# martix_connect.net
KiCad netlist of a schematic drawn in Altium Designer
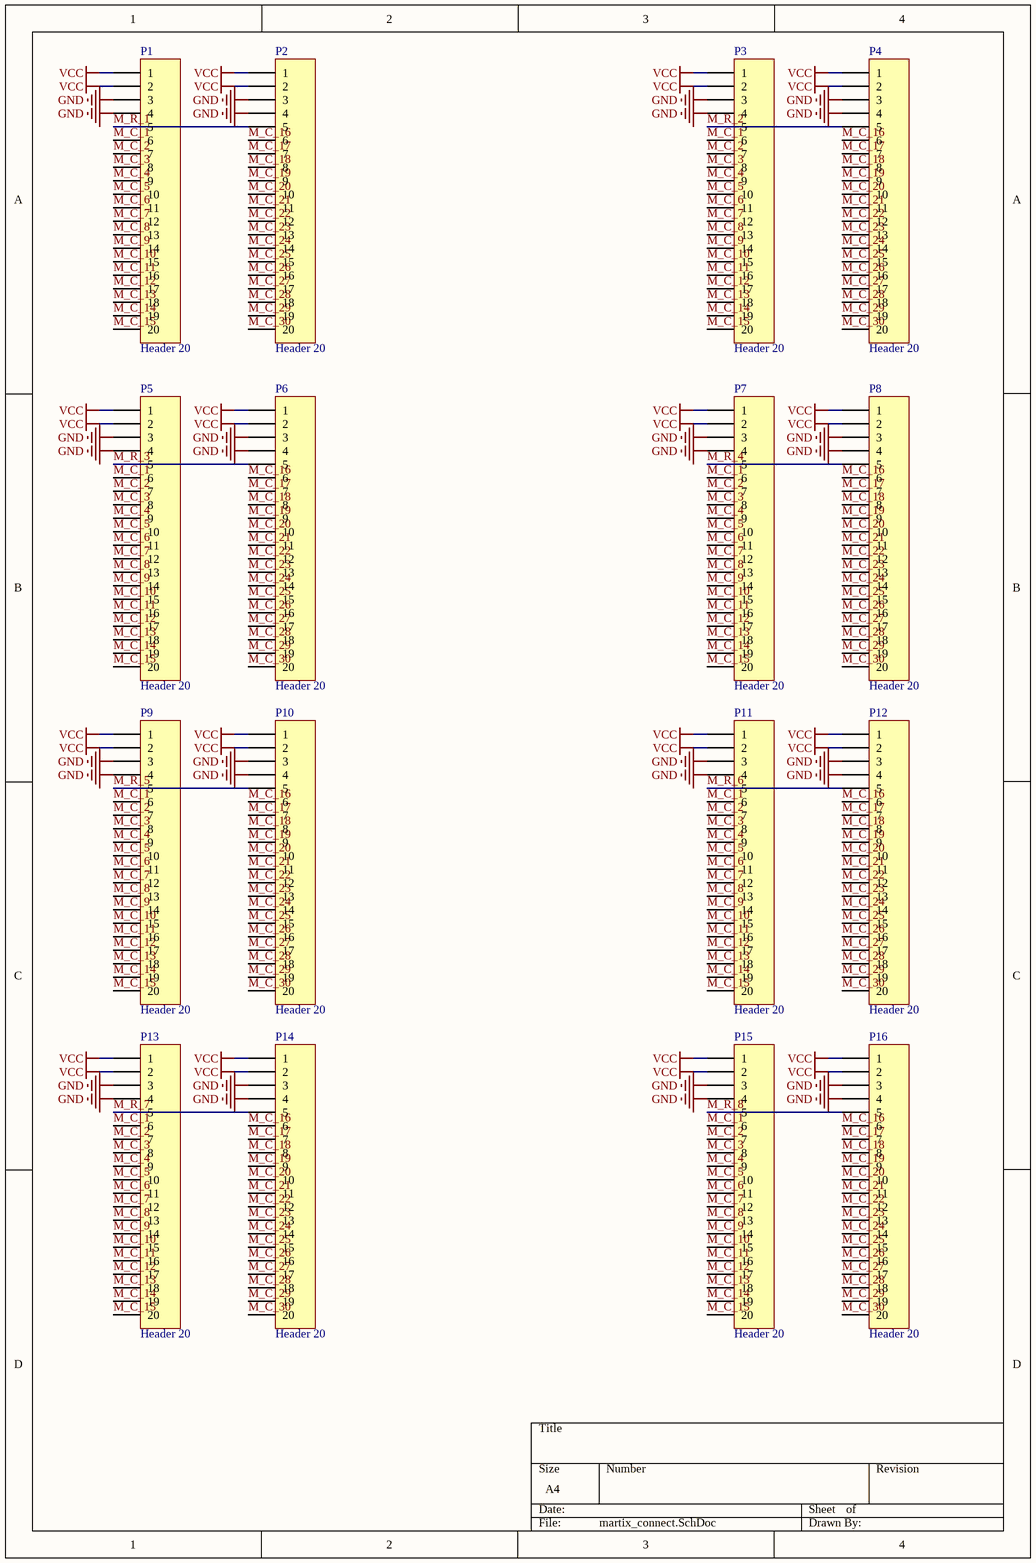
[diagram p0: martix_connect.SchDoc]

(export (version "E")
  (design (tool "Eeschema 10.0.6"))
  (components
    (comp (ref "P1")
      (value "Header 20")
      (footprint "FPC0.5 2H-WS-20P")
      (description "Header, 20-Pin")
      (fields (field (name "PUBLISHER") "Altium Limited"))
      (libsource (lib "Miscellaneous Connectors") (part "Header 20"))
    )
    (comp (ref "P2")
      (value "Header 20")
      (footprint "FPC0.5 2H-WS-20P")
      (description "Header, 20-Pin")
      (fields (field (name "PUBLISHER") "Altium Limited"))
      (libsource (lib "Miscellaneous Connectors") (part "Header 20"))
    )
    (comp (ref "P3")
      (value "Header 20")
      (footprint "FPC0.5 2H-WS-20P")
      (description "Header, 20-Pin")
      (fields (field (name "PUBLISHER") "Altium Limited"))
      (libsource (lib "Miscellaneous Connectors") (part "Header 20"))
    )
    (comp (ref "P4")
      (value "Header 20")
      (footprint "FPC0.5 2H-WS-20P")
      (description "Header, 20-Pin")
      (fields (field (name "PUBLISHER") "Altium Limited"))
      (libsource (lib "Miscellaneous Connectors") (part "Header 20"))
    )
    (comp (ref "P5")
      (value "Header 20")
      (footprint "FPC0.5 2H-WS-20P")
      (description "Header, 20-Pin")
      (fields (field (name "PUBLISHER") "Altium Limited"))
      (libsource (lib "Miscellaneous Connectors") (part "Header 20"))
    )
    (comp (ref "P6")
      (value "Header 20")
      (footprint "FPC0.5 2H-WS-20P")
      (description "Header, 20-Pin")
      (fields (field (name "PUBLISHER") "Altium Limited"))
      (libsource (lib "Miscellaneous Connectors") (part "Header 20"))
    )
    (comp (ref "P7")
      (value "Header 20")
      (footprint "FPC0.5 2H-WS-20P")
      (description "Header, 20-Pin")
      (fields (field (name "PUBLISHER") "Altium Limited"))
      (libsource (lib "Miscellaneous Connectors") (part "Header 20"))
    )
    (comp (ref "P8")
      (value "Header 20")
      (footprint "FPC0.5 2H-WS-20P")
      (description "Header, 20-Pin")
      (fields (field (name "PUBLISHER") "Altium Limited"))
      (libsource (lib "Miscellaneous Connectors") (part "Header 20"))
    )
    (comp (ref "P9")
      (value "Header 20")
      (footprint "FPC0.5 2H-WS-20P")
      (description "Header, 20-Pin")
      (fields (field (name "PUBLISHER") "Altium Limited"))
      (libsource (lib "Miscellaneous Connectors") (part "Header 20"))
    )
    (comp (ref "P10")
      (value "Header 20")
      (footprint "FPC0.5 2H-WS-20P")
      (description "Header, 20-Pin")
      (fields (field (name "PUBLISHER") "Altium Limited"))
      (libsource (lib "Miscellaneous Connectors") (part "Header 20"))
    )
    (comp (ref "P11")
      (value "Header 20")
      (footprint "FPC0.5 2H-WS-20P")
      (description "Header, 20-Pin")
      (fields (field (name "PUBLISHER") "Altium Limited"))
      (libsource (lib "Miscellaneous Connectors") (part "Header 20"))
    )
    (comp (ref "P12")
      (value "Header 20")
      (footprint "FPC0.5 2H-WS-20P")
      (description "Header, 20-Pin")
      (fields (field (name "PUBLISHER") "Altium Limited"))
      (libsource (lib "Miscellaneous Connectors") (part "Header 20"))
    )
    (comp (ref "P13")
      (value "Header 20")
      (footprint "FPC0.5 2H-WS-20P")
      (description "Header, 20-Pin")
      (fields (field (name "PUBLISHER") "Altium Limited"))
      (libsource (lib "Miscellaneous Connectors") (part "Header 20"))
    )
    (comp (ref "P14")
      (value "Header 20")
      (footprint "FPC0.5 2H-WS-20P")
      (description "Header, 20-Pin")
      (fields (field (name "PUBLISHER") "Altium Limited"))
      (libsource (lib "Miscellaneous Connectors") (part "Header 20"))
    )
    (comp (ref "P15")
      (value "Header 20")
      (footprint "FPC0.5 2H-WS-20P")
      (description "Header, 20-Pin")
      (fields (field (name "PUBLISHER") "Altium Limited"))
      (libsource (lib "Miscellaneous Connectors") (part "Header 20"))
    )
    (comp (ref "P16")
      (value "Header 20")
      (footprint "FPC0.5 2H-WS-20P")
      (description "Header, 20-Pin")
      (fields (field (name "PUBLISHER") "Altium Limited"))
      (libsource (lib "Miscellaneous Connectors") (part "Header 20"))
    )
  )
  (nets
    (net (code "1") (name "/M_C_1") (class "Default")
      (node (ref "P1") (pin "6") (pinfunction "6_6") (pintype "passive"))
      (node (ref "P11") (pin "6") (pinfunction "6_6") (pintype "passive"))
      (node (ref "P13") (pin "6") (pinfunction "6_6") (pintype "passive"))
      (node (ref "P15") (pin "6") (pinfunction "6_6") (pintype "passive"))
      (node (ref "P3") (pin "6") (pinfunction "6_6") (pintype "passive"))
      (node (ref "P5") (pin "6") (pinfunction "6_6") (pintype "passive"))
      (node (ref "P7") (pin "6") (pinfunction "6_6") (pintype "passive"))
      (node (ref "P9") (pin "6") (pinfunction "6_6") (pintype "passive"))
    )
    (net (code "2") (name "/M_C_2") (class "Default")
      (node (ref "P1") (pin "7") (pinfunction "7_7") (pintype "passive"))
      (node (ref "P11") (pin "7") (pinfunction "7_7") (pintype "passive"))
      (node (ref "P13") (pin "7") (pinfunction "7_7") (pintype "passive"))
      (node (ref "P15") (pin "7") (pinfunction "7_7") (pintype "passive"))
      (node (ref "P3") (pin "7") (pinfunction "7_7") (pintype "passive"))
      (node (ref "P5") (pin "7") (pinfunction "7_7") (pintype "passive"))
      (node (ref "P7") (pin "7") (pinfunction "7_7") (pintype "passive"))
      (node (ref "P9") (pin "7") (pinfunction "7_7") (pintype "passive"))
    )
    (net (code "3") (name "/M_C_3") (class "Default")
      (node (ref "P1") (pin "8") (pinfunction "8_8") (pintype "passive"))
      (node (ref "P11") (pin "8") (pinfunction "8_8") (pintype "passive"))
      (node (ref "P13") (pin "8") (pinfunction "8_8") (pintype "passive"))
      (node (ref "P15") (pin "8") (pinfunction "8_8") (pintype "passive"))
      (node (ref "P3") (pin "8") (pinfunction "8_8") (pintype "passive"))
      (node (ref "P5") (pin "8") (pinfunction "8_8") (pintype "passive"))
      (node (ref "P7") (pin "8") (pinfunction "8_8") (pintype "passive"))
      (node (ref "P9") (pin "8") (pinfunction "8_8") (pintype "passive"))
    )
    (net (code "4") (name "/M_C_4") (class "Default")
      (node (ref "P1") (pin "9") (pinfunction "9_9") (pintype "passive"))
      (node (ref "P11") (pin "9") (pinfunction "9_9") (pintype "passive"))
      (node (ref "P13") (pin "9") (pinfunction "9_9") (pintype "passive"))
      (node (ref "P15") (pin "9") (pinfunction "9_9") (pintype "passive"))
      (node (ref "P3") (pin "9") (pinfunction "9_9") (pintype "passive"))
      (node (ref "P5") (pin "9") (pinfunction "9_9") (pintype "passive"))
      (node (ref "P7") (pin "9") (pinfunction "9_9") (pintype "passive"))
      (node (ref "P9") (pin "9") (pinfunction "9_9") (pintype "passive"))
    )
    (net (code "5") (name "/M_C_5") (class "Default")
      (node (ref "P1") (pin "10") (pinfunction "10_10") (pintype "passive"))
      (node (ref "P11") (pin "10") (pinfunction "10_10") (pintype "passive"))
      (node (ref "P13") (pin "10") (pinfunction "10_10") (pintype "passive"))
      (node (ref "P15") (pin "10") (pinfunction "10_10") (pintype "passive"))
      (node (ref "P3") (pin "10") (pinfunction "10_10") (pintype "passive"))
      (node (ref "P5") (pin "10") (pinfunction "10_10") (pintype "passive"))
      (node (ref "P7") (pin "10") (pinfunction "10_10") (pintype "passive"))
      (node (ref "P9") (pin "10") (pinfunction "10_10") (pintype "passive"))
    )
    (net (code "6") (name "/M_C_6") (class "Default")
      (node (ref "P1") (pin "11") (pinfunction "11_11") (pintype "passive"))
      (node (ref "P11") (pin "11") (pinfunction "11_11") (pintype "passive"))
      (node (ref "P13") (pin "11") (pinfunction "11_11") (pintype "passive"))
      (node (ref "P15") (pin "11") (pinfunction "11_11") (pintype "passive"))
      (node (ref "P3") (pin "11") (pinfunction "11_11") (pintype "passive"))
      (node (ref "P5") (pin "11") (pinfunction "11_11") (pintype "passive"))
      (node (ref "P7") (pin "11") (pinfunction "11_11") (pintype "passive"))
      (node (ref "P9") (pin "11") (pinfunction "11_11") (pintype "passive"))
    )
    (net (code "7") (name "/M_C_7") (class "Default")
      (node (ref "P1") (pin "12") (pinfunction "12_12") (pintype "passive"))
      (node (ref "P11") (pin "12") (pinfunction "12_12") (pintype "passive"))
      (node (ref "P13") (pin "12") (pinfunction "12_12") (pintype "passive"))
      (node (ref "P15") (pin "12") (pinfunction "12_12") (pintype "passive"))
      (node (ref "P3") (pin "12") (pinfunction "12_12") (pintype "passive"))
      (node (ref "P5") (pin "12") (pinfunction "12_12") (pintype "passive"))
      (node (ref "P7") (pin "12") (pinfunction "12_12") (pintype "passive"))
      (node (ref "P9") (pin "12") (pinfunction "12_12") (pintype "passive"))
    )
    (net (code "8") (name "/M_C_8") (class "Default")
      (node (ref "P1") (pin "13") (pinfunction "13_13") (pintype "passive"))
      (node (ref "P11") (pin "13") (pinfunction "13_13") (pintype "passive"))
      (node (ref "P13") (pin "13") (pinfunction "13_13") (pintype "passive"))
      (node (ref "P15") (pin "13") (pinfunction "13_13") (pintype "passive"))
      (node (ref "P3") (pin "13") (pinfunction "13_13") (pintype "passive"))
      (node (ref "P5") (pin "13") (pinfunction "13_13") (pintype "passive"))
      (node (ref "P7") (pin "13") (pinfunction "13_13") (pintype "passive"))
      (node (ref "P9") (pin "13") (pinfunction "13_13") (pintype "passive"))
    )
    (net (code "9") (name "/M_C_9") (class "Default")
      (node (ref "P1") (pin "14") (pinfunction "14_14") (pintype "passive"))
      (node (ref "P11") (pin "14") (pinfunction "14_14") (pintype "passive"))
      (node (ref "P13") (pin "14") (pinfunction "14_14") (pintype "passive"))
      (node (ref "P15") (pin "14") (pinfunction "14_14") (pintype "passive"))
      (node (ref "P3") (pin "14") (pinfunction "14_14") (pintype "passive"))
      (node (ref "P5") (pin "14") (pinfunction "14_14") (pintype "passive"))
      (node (ref "P7") (pin "14") (pinfunction "14_14") (pintype "passive"))
      (node (ref "P9") (pin "14") (pinfunction "14_14") (pintype "passive"))
    )
    (net (code "10") (name "/M_C_10") (class "Default")
      (node (ref "P1") (pin "15") (pinfunction "15_15") (pintype "passive"))
      (node (ref "P11") (pin "15") (pinfunction "15_15") (pintype "passive"))
      (node (ref "P13") (pin "15") (pinfunction "15_15") (pintype "passive"))
      (node (ref "P15") (pin "15") (pinfunction "15_15") (pintype "passive"))
      (node (ref "P3") (pin "15") (pinfunction "15_15") (pintype "passive"))
      (node (ref "P5") (pin "15") (pinfunction "15_15") (pintype "passive"))
      (node (ref "P7") (pin "15") (pinfunction "15_15") (pintype "passive"))
      (node (ref "P9") (pin "15") (pinfunction "15_15") (pintype "passive"))
    )
    (net (code "11") (name "/M_C_11") (class "Default")
      (node (ref "P1") (pin "16") (pinfunction "16_16") (pintype "passive"))
      (node (ref "P11") (pin "16") (pinfunction "16_16") (pintype "passive"))
      (node (ref "P13") (pin "16") (pinfunction "16_16") (pintype "passive"))
      (node (ref "P15") (pin "16") (pinfunction "16_16") (pintype "passive"))
      (node (ref "P3") (pin "16") (pinfunction "16_16") (pintype "passive"))
      (node (ref "P5") (pin "16") (pinfunction "16_16") (pintype "passive"))
      (node (ref "P7") (pin "16") (pinfunction "16_16") (pintype "passive"))
      (node (ref "P9") (pin "16") (pinfunction "16_16") (pintype "passive"))
    )
    (net (code "12") (name "/M_C_12") (class "Default")
      (node (ref "P1") (pin "17") (pinfunction "17_17") (pintype "passive"))
      (node (ref "P11") (pin "17") (pinfunction "17_17") (pintype "passive"))
      (node (ref "P13") (pin "17") (pinfunction "17_17") (pintype "passive"))
      (node (ref "P15") (pin "17") (pinfunction "17_17") (pintype "passive"))
      (node (ref "P3") (pin "17") (pinfunction "17_17") (pintype "passive"))
      (node (ref "P5") (pin "17") (pinfunction "17_17") (pintype "passive"))
      (node (ref "P7") (pin "17") (pinfunction "17_17") (pintype "passive"))
      (node (ref "P9") (pin "17") (pinfunction "17_17") (pintype "passive"))
    )
    (net (code "13") (name "/M_C_13") (class "Default")
      (node (ref "P1") (pin "18") (pinfunction "18_18") (pintype "passive"))
      (node (ref "P11") (pin "18") (pinfunction "18_18") (pintype "passive"))
      (node (ref "P13") (pin "18") (pinfunction "18_18") (pintype "passive"))
      (node (ref "P15") (pin "18") (pinfunction "18_18") (pintype "passive"))
      (node (ref "P3") (pin "18") (pinfunction "18_18") (pintype "passive"))
      (node (ref "P5") (pin "18") (pinfunction "18_18") (pintype "passive"))
      (node (ref "P7") (pin "18") (pinfunction "18_18") (pintype "passive"))
      (node (ref "P9") (pin "18") (pinfunction "18_18") (pintype "passive"))
    )
    (net (code "14") (name "/M_C_14") (class "Default")
      (node (ref "P1") (pin "19") (pinfunction "19_19") (pintype "passive"))
      (node (ref "P11") (pin "19") (pinfunction "19_19") (pintype "passive"))
      (node (ref "P13") (pin "19") (pinfunction "19_19") (pintype "passive"))
      (node (ref "P15") (pin "19") (pinfunction "19_19") (pintype "passive"))
      (node (ref "P3") (pin "19") (pinfunction "19_19") (pintype "passive"))
      (node (ref "P5") (pin "19") (pinfunction "19_19") (pintype "passive"))
      (node (ref "P7") (pin "19") (pinfunction "19_19") (pintype "passive"))
      (node (ref "P9") (pin "19") (pinfunction "19_19") (pintype "passive"))
    )
    (net (code "15") (name "/M_C_15") (class "Default")
      (node (ref "P1") (pin "20") (pinfunction "20_20") (pintype "passive"))
      (node (ref "P11") (pin "20") (pinfunction "20_20") (pintype "passive"))
      (node (ref "P13") (pin "20") (pinfunction "20_20") (pintype "passive"))
      (node (ref "P15") (pin "20") (pinfunction "20_20") (pintype "passive"))
      (node (ref "P3") (pin "20") (pinfunction "20_20") (pintype "passive"))
      (node (ref "P5") (pin "20") (pinfunction "20_20") (pintype "passive"))
      (node (ref "P7") (pin "20") (pinfunction "20_20") (pintype "passive"))
      (node (ref "P9") (pin "20") (pinfunction "20_20") (pintype "passive"))
    )
    (net (code "16") (name "/M_C_16") (class "Default")
      (node (ref "P10") (pin "6") (pinfunction "6_6") (pintype "passive"))
      (node (ref "P12") (pin "6") (pinfunction "6_6") (pintype "passive"))
      (node (ref "P14") (pin "6") (pinfunction "6_6") (pintype "passive"))
      (node (ref "P16") (pin "6") (pinfunction "6_6") (pintype "passive"))
      (node (ref "P2") (pin "6") (pinfunction "6_6") (pintype "passive"))
      (node (ref "P4") (pin "6") (pinfunction "6_6") (pintype "passive"))
      (node (ref "P6") (pin "6") (pinfunction "6_6") (pintype "passive"))
      (node (ref "P8") (pin "6") (pinfunction "6_6") (pintype "passive"))
    )
    (net (code "17") (name "/M_C_17") (class "Default")
      (node (ref "P10") (pin "7") (pinfunction "7_7") (pintype "passive"))
      (node (ref "P12") (pin "7") (pinfunction "7_7") (pintype "passive"))
      (node (ref "P14") (pin "7") (pinfunction "7_7") (pintype "passive"))
      (node (ref "P16") (pin "7") (pinfunction "7_7") (pintype "passive"))
      (node (ref "P2") (pin "7") (pinfunction "7_7") (pintype "passive"))
      (node (ref "P4") (pin "7") (pinfunction "7_7") (pintype "passive"))
      (node (ref "P6") (pin "7") (pinfunction "7_7") (pintype "passive"))
      (node (ref "P8") (pin "7") (pinfunction "7_7") (pintype "passive"))
    )
    (net (code "18") (name "/M_C_18") (class "Default")
      (node (ref "P10") (pin "8") (pinfunction "8_8") (pintype "passive"))
      (node (ref "P12") (pin "8") (pinfunction "8_8") (pintype "passive"))
      (node (ref "P14") (pin "8") (pinfunction "8_8") (pintype "passive"))
      (node (ref "P16") (pin "8") (pinfunction "8_8") (pintype "passive"))
      (node (ref "P2") (pin "8") (pinfunction "8_8") (pintype "passive"))
      (node (ref "P4") (pin "8") (pinfunction "8_8") (pintype "passive"))
      (node (ref "P6") (pin "8") (pinfunction "8_8") (pintype "passive"))
      (node (ref "P8") (pin "8") (pinfunction "8_8") (pintype "passive"))
    )
    (net (code "19") (name "/M_C_19") (class "Default")
      (node (ref "P10") (pin "9") (pinfunction "9_9") (pintype "passive"))
      (node (ref "P12") (pin "9") (pinfunction "9_9") (pintype "passive"))
      (node (ref "P14") (pin "9") (pinfunction "9_9") (pintype "passive"))
      (node (ref "P16") (pin "9") (pinfunction "9_9") (pintype "passive"))
      (node (ref "P2") (pin "9") (pinfunction "9_9") (pintype "passive"))
      (node (ref "P4") (pin "9") (pinfunction "9_9") (pintype "passive"))
      (node (ref "P6") (pin "9") (pinfunction "9_9") (pintype "passive"))
      (node (ref "P8") (pin "9") (pinfunction "9_9") (pintype "passive"))
    )
    (net (code "20") (name "/M_C_20") (class "Default")
      (node (ref "P10") (pin "10") (pinfunction "10_10") (pintype "passive"))
      (node (ref "P12") (pin "10") (pinfunction "10_10") (pintype "passive"))
      (node (ref "P14") (pin "10") (pinfunction "10_10") (pintype "passive"))
      (node (ref "P16") (pin "10") (pinfunction "10_10") (pintype "passive"))
      (node (ref "P2") (pin "10") (pinfunction "10_10") (pintype "passive"))
      (node (ref "P4") (pin "10") (pinfunction "10_10") (pintype "passive"))
      (node (ref "P6") (pin "10") (pinfunction "10_10") (pintype "passive"))
      (node (ref "P8") (pin "10") (pinfunction "10_10") (pintype "passive"))
    )
    (net (code "21") (name "/M_C_21") (class "Default")
      (node (ref "P10") (pin "11") (pinfunction "11_11") (pintype "passive"))
      (node (ref "P12") (pin "11") (pinfunction "11_11") (pintype "passive"))
      (node (ref "P14") (pin "11") (pinfunction "11_11") (pintype "passive"))
      (node (ref "P16") (pin "11") (pinfunction "11_11") (pintype "passive"))
      (node (ref "P2") (pin "11") (pinfunction "11_11") (pintype "passive"))
      (node (ref "P4") (pin "11") (pinfunction "11_11") (pintype "passive"))
      (node (ref "P6") (pin "11") (pinfunction "11_11") (pintype "passive"))
      (node (ref "P8") (pin "11") (pinfunction "11_11") (pintype "passive"))
    )
    (net (code "22") (name "/M_C_22") (class "Default")
      (node (ref "P10") (pin "12") (pinfunction "12_12") (pintype "passive"))
      (node (ref "P12") (pin "12") (pinfunction "12_12") (pintype "passive"))
      (node (ref "P14") (pin "12") (pinfunction "12_12") (pintype "passive"))
      (node (ref "P16") (pin "12") (pinfunction "12_12") (pintype "passive"))
      (node (ref "P2") (pin "12") (pinfunction "12_12") (pintype "passive"))
      (node (ref "P4") (pin "12") (pinfunction "12_12") (pintype "passive"))
      (node (ref "P6") (pin "12") (pinfunction "12_12") (pintype "passive"))
      (node (ref "P8") (pin "12") (pinfunction "12_12") (pintype "passive"))
    )
    (net (code "23") (name "/M_C_23") (class "Default")
      (node (ref "P10") (pin "13") (pinfunction "13_13") (pintype "passive"))
      (node (ref "P12") (pin "13") (pinfunction "13_13") (pintype "passive"))
      (node (ref "P14") (pin "13") (pinfunction "13_13") (pintype "passive"))
      (node (ref "P16") (pin "13") (pinfunction "13_13") (pintype "passive"))
      (node (ref "P2") (pin "13") (pinfunction "13_13") (pintype "passive"))
      (node (ref "P4") (pin "13") (pinfunction "13_13") (pintype "passive"))
      (node (ref "P6") (pin "13") (pinfunction "13_13") (pintype "passive"))
      (node (ref "P8") (pin "13") (pinfunction "13_13") (pintype "passive"))
    )
    (net (code "24") (name "/M_C_24") (class "Default")
      (node (ref "P10") (pin "14") (pinfunction "14_14") (pintype "passive"))
      (node (ref "P12") (pin "14") (pinfunction "14_14") (pintype "passive"))
      (node (ref "P14") (pin "14") (pinfunction "14_14") (pintype "passive"))
      (node (ref "P16") (pin "14") (pinfunction "14_14") (pintype "passive"))
      (node (ref "P2") (pin "14") (pinfunction "14_14") (pintype "passive"))
      (node (ref "P4") (pin "14") (pinfunction "14_14") (pintype "passive"))
      (node (ref "P6") (pin "14") (pinfunction "14_14") (pintype "passive"))
      (node (ref "P8") (pin "14") (pinfunction "14_14") (pintype "passive"))
    )
    (net (code "25") (name "/M_C_25") (class "Default")
      (node (ref "P10") (pin "15") (pinfunction "15_15") (pintype "passive"))
      (node (ref "P12") (pin "15") (pinfunction "15_15") (pintype "passive"))
      (node (ref "P14") (pin "15") (pinfunction "15_15") (pintype "passive"))
      (node (ref "P16") (pin "15") (pinfunction "15_15") (pintype "passive"))
      (node (ref "P2") (pin "15") (pinfunction "15_15") (pintype "passive"))
      (node (ref "P4") (pin "15") (pinfunction "15_15") (pintype "passive"))
      (node (ref "P6") (pin "15") (pinfunction "15_15") (pintype "passive"))
      (node (ref "P8") (pin "15") (pinfunction "15_15") (pintype "passive"))
    )
    (net (code "26") (name "/M_C_26") (class "Default")
      (node (ref "P10") (pin "16") (pinfunction "16_16") (pintype "passive"))
      (node (ref "P12") (pin "16") (pinfunction "16_16") (pintype "passive"))
      (node (ref "P14") (pin "16") (pinfunction "16_16") (pintype "passive"))
      (node (ref "P16") (pin "16") (pinfunction "16_16") (pintype "passive"))
      (node (ref "P2") (pin "16") (pinfunction "16_16") (pintype "passive"))
      (node (ref "P4") (pin "16") (pinfunction "16_16") (pintype "passive"))
      (node (ref "P6") (pin "16") (pinfunction "16_16") (pintype "passive"))
      (node (ref "P8") (pin "16") (pinfunction "16_16") (pintype "passive"))
    )
    (net (code "27") (name "/M_C_27") (class "Default")
      (node (ref "P10") (pin "17") (pinfunction "17_17") (pintype "passive"))
      (node (ref "P12") (pin "17") (pinfunction "17_17") (pintype "passive"))
      (node (ref "P14") (pin "17") (pinfunction "17_17") (pintype "passive"))
      (node (ref "P16") (pin "17") (pinfunction "17_17") (pintype "passive"))
      (node (ref "P2") (pin "17") (pinfunction "17_17") (pintype "passive"))
      (node (ref "P4") (pin "17") (pinfunction "17_17") (pintype "passive"))
      (node (ref "P6") (pin "17") (pinfunction "17_17") (pintype "passive"))
      (node (ref "P8") (pin "17") (pinfunction "17_17") (pintype "passive"))
    )
    (net (code "28") (name "/M_C_28") (class "Default")
      (node (ref "P10") (pin "18") (pinfunction "18_18") (pintype "passive"))
      (node (ref "P12") (pin "18") (pinfunction "18_18") (pintype "passive"))
      (node (ref "P14") (pin "18") (pinfunction "18_18") (pintype "passive"))
      (node (ref "P16") (pin "18") (pinfunction "18_18") (pintype "passive"))
      (node (ref "P2") (pin "18") (pinfunction "18_18") (pintype "passive"))
      (node (ref "P4") (pin "18") (pinfunction "18_18") (pintype "passive"))
      (node (ref "P6") (pin "18") (pinfunction "18_18") (pintype "passive"))
      (node (ref "P8") (pin "18") (pinfunction "18_18") (pintype "passive"))
    )
    (net (code "29") (name "/M_C_29") (class "Default")
      (node (ref "P10") (pin "19") (pinfunction "19_19") (pintype "passive"))
      (node (ref "P12") (pin "19") (pinfunction "19_19") (pintype "passive"))
      (node (ref "P14") (pin "19") (pinfunction "19_19") (pintype "passive"))
      (node (ref "P16") (pin "19") (pinfunction "19_19") (pintype "passive"))
      (node (ref "P2") (pin "19") (pinfunction "19_19") (pintype "passive"))
      (node (ref "P4") (pin "19") (pinfunction "19_19") (pintype "passive"))
      (node (ref "P6") (pin "19") (pinfunction "19_19") (pintype "passive"))
      (node (ref "P8") (pin "19") (pinfunction "19_19") (pintype "passive"))
    )
    (net (code "30") (name "/M_C_30") (class "Default")
      (node (ref "P10") (pin "20") (pinfunction "20_20") (pintype "passive"))
      (node (ref "P12") (pin "20") (pinfunction "20_20") (pintype "passive"))
      (node (ref "P14") (pin "20") (pinfunction "20_20") (pintype "passive"))
      (node (ref "P16") (pin "20") (pinfunction "20_20") (pintype "passive"))
      (node (ref "P2") (pin "20") (pinfunction "20_20") (pintype "passive"))
      (node (ref "P4") (pin "20") (pinfunction "20_20") (pintype "passive"))
      (node (ref "P6") (pin "20") (pinfunction "20_20") (pintype "passive"))
      (node (ref "P8") (pin "20") (pinfunction "20_20") (pintype "passive"))
    )
    (net (code "31") (name "/M_R_1") (class "Default")
      (node (ref "P1") (pin "5") (pinfunction "5_5") (pintype "passive"))
      (node (ref "P2") (pin "5") (pinfunction "5_5") (pintype "passive"))
    )
    (net (code "32") (name "/M_R_2") (class "Default")
      (node (ref "P3") (pin "5") (pinfunction "5_5") (pintype "passive"))
      (node (ref "P4") (pin "5") (pinfunction "5_5") (pintype "passive"))
    )
    (net (code "33") (name "/M_R_3") (class "Default")
      (node (ref "P5") (pin "5") (pinfunction "5_5") (pintype "passive"))
      (node (ref "P6") (pin "5") (pinfunction "5_5") (pintype "passive"))
    )
    (net (code "34") (name "/M_R_4") (class "Default")
      (node (ref "P7") (pin "5") (pinfunction "5_5") (pintype "passive"))
      (node (ref "P8") (pin "5") (pinfunction "5_5") (pintype "passive"))
    )
    (net (code "35") (name "/M_R_5") (class "Default")
      (node (ref "P10") (pin "5") (pinfunction "5_5") (pintype "passive"))
      (node (ref "P9") (pin "5") (pinfunction "5_5") (pintype "passive"))
    )
    (net (code "36") (name "/M_R_6") (class "Default")
      (node (ref "P11") (pin "5") (pinfunction "5_5") (pintype "passive"))
      (node (ref "P12") (pin "5") (pinfunction "5_5") (pintype "passive"))
    )
    (net (code "37") (name "/M_R_7") (class "Default")
      (node (ref "P13") (pin "5") (pinfunction "5_5") (pintype "passive"))
      (node (ref "P14") (pin "5") (pinfunction "5_5") (pintype "passive"))
    )
    (net (code "38") (name "/M_R_8") (class "Default")
      (node (ref "P15") (pin "5") (pinfunction "5_5") (pintype "passive"))
      (node (ref "P16") (pin "5") (pinfunction "5_5") (pintype "passive"))
    )
    (net (code "39") (name "GND") (class "Default")
      (node (ref "P1") (pin "3") (pinfunction "3_3") (pintype "passive"))
      (node (ref "P1") (pin "4") (pinfunction "4_4") (pintype "passive"))
      (node (ref "P10") (pin "3") (pinfunction "3_3") (pintype "passive"))
      (node (ref "P10") (pin "4") (pinfunction "4_4") (pintype "passive"))
      (node (ref "P11") (pin "3") (pinfunction "3_3") (pintype "passive"))
      (node (ref "P11") (pin "4") (pinfunction "4_4") (pintype "passive"))
      (node (ref "P12") (pin "3") (pinfunction "3_3") (pintype "passive"))
      (node (ref "P12") (pin "4") (pinfunction "4_4") (pintype "passive"))
      (node (ref "P13") (pin "3") (pinfunction "3_3") (pintype "passive"))
      (node (ref "P13") (pin "4") (pinfunction "4_4") (pintype "passive"))
      (node (ref "P14") (pin "3") (pinfunction "3_3") (pintype "passive"))
      (node (ref "P14") (pin "4") (pinfunction "4_4") (pintype "passive"))
      (node (ref "P15") (pin "3") (pinfunction "3_3") (pintype "passive"))
      (node (ref "P15") (pin "4") (pinfunction "4_4") (pintype "passive"))
      (node (ref "P16") (pin "3") (pinfunction "3_3") (pintype "passive"))
      (node (ref "P16") (pin "4") (pinfunction "4_4") (pintype "passive"))
      (node (ref "P2") (pin "3") (pinfunction "3_3") (pintype "passive"))
      (node (ref "P2") (pin "4") (pinfunction "4_4") (pintype "passive"))
      (node (ref "P3") (pin "3") (pinfunction "3_3") (pintype "passive"))
      (node (ref "P3") (pin "4") (pinfunction "4_4") (pintype "passive"))
      (node (ref "P4") (pin "3") (pinfunction "3_3") (pintype "passive"))
      (node (ref "P4") (pin "4") (pinfunction "4_4") (pintype "passive"))
      (node (ref "P5") (pin "3") (pinfunction "3_3") (pintype "passive"))
      (node (ref "P5") (pin "4") (pinfunction "4_4") (pintype "passive"))
      (node (ref "P6") (pin "3") (pinfunction "3_3") (pintype "passive"))
      (node (ref "P6") (pin "4") (pinfunction "4_4") (pintype "passive"))
      (node (ref "P7") (pin "3") (pinfunction "3_3") (pintype "passive"))
      (node (ref "P7") (pin "4") (pinfunction "4_4") (pintype "passive"))
      (node (ref "P8") (pin "3") (pinfunction "3_3") (pintype "passive"))
      (node (ref "P8") (pin "4") (pinfunction "4_4") (pintype "passive"))
      (node (ref "P9") (pin "3") (pinfunction "3_3") (pintype "passive"))
      (node (ref "P9") (pin "4") (pinfunction "4_4") (pintype "passive"))
    )
    (net (code "40") (name "VCC") (class "Default")
      (node (ref "P1") (pin "1") (pinfunction "1_1") (pintype "passive"))
      (node (ref "P1") (pin "2") (pinfunction "2_2") (pintype "passive"))
      (node (ref "P10") (pin "1") (pinfunction "1_1") (pintype "passive"))
      (node (ref "P10") (pin "2") (pinfunction "2_2") (pintype "passive"))
      (node (ref "P11") (pin "1") (pinfunction "1_1") (pintype "passive"))
      (node (ref "P11") (pin "2") (pinfunction "2_2") (pintype "passive"))
      (node (ref "P12") (pin "1") (pinfunction "1_1") (pintype "passive"))
      (node (ref "P12") (pin "2") (pinfunction "2_2") (pintype "passive"))
      (node (ref "P13") (pin "1") (pinfunction "1_1") (pintype "passive"))
      (node (ref "P13") (pin "2") (pinfunction "2_2") (pintype "passive"))
      (node (ref "P14") (pin "1") (pinfunction "1_1") (pintype "passive"))
      (node (ref "P14") (pin "2") (pinfunction "2_2") (pintype "passive"))
      (node (ref "P15") (pin "1") (pinfunction "1_1") (pintype "passive"))
      (node (ref "P15") (pin "2") (pinfunction "2_2") (pintype "passive"))
      (node (ref "P16") (pin "1") (pinfunction "1_1") (pintype "passive"))
      (node (ref "P16") (pin "2") (pinfunction "2_2") (pintype "passive"))
      (node (ref "P2") (pin "1") (pinfunction "1_1") (pintype "passive"))
      (node (ref "P2") (pin "2") (pinfunction "2_2") (pintype "passive"))
      (node (ref "P3") (pin "1") (pinfunction "1_1") (pintype "passive"))
      (node (ref "P3") (pin "2") (pinfunction "2_2") (pintype "passive"))
      (node (ref "P4") (pin "1") (pinfunction "1_1") (pintype "passive"))
      (node (ref "P4") (pin "2") (pinfunction "2_2") (pintype "passive"))
      (node (ref "P5") (pin "1") (pinfunction "1_1") (pintype "passive"))
      (node (ref "P5") (pin "2") (pinfunction "2_2") (pintype "passive"))
      (node (ref "P6") (pin "1") (pinfunction "1_1") (pintype "passive"))
      (node (ref "P6") (pin "2") (pinfunction "2_2") (pintype "passive"))
      (node (ref "P7") (pin "1") (pinfunction "1_1") (pintype "passive"))
      (node (ref "P7") (pin "2") (pinfunction "2_2") (pintype "passive"))
      (node (ref "P8") (pin "1") (pinfunction "1_1") (pintype "passive"))
      (node (ref "P8") (pin "2") (pinfunction "2_2") (pintype "passive"))
      (node (ref "P9") (pin "1") (pinfunction "1_1") (pintype "passive"))
      (node (ref "P9") (pin "2") (pinfunction "2_2") (pintype "passive"))
    )
  )
)
